# Connecteur.net
KiCad netlist of a schematic drawn in Altium Designer
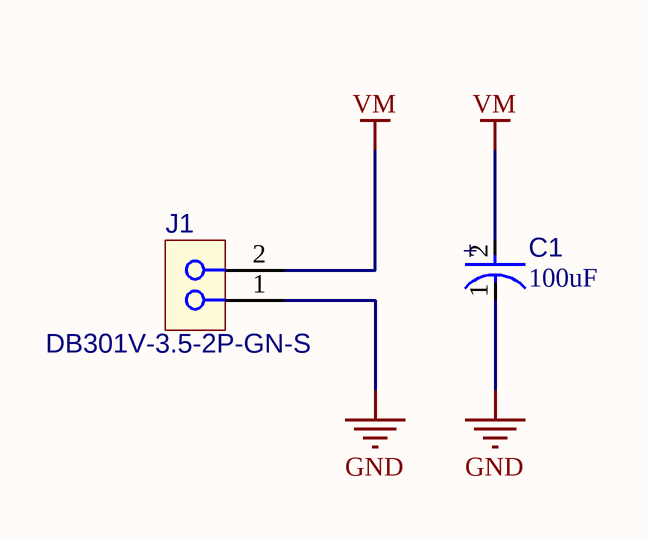
[diagram p0: Connecteur.SchDoc]

(export (version "E")
  (design (tool "Eeschema 10.0.6"))
  (components
    (comp (ref "C1")
      (value "100uF")
      (footprint "C_EL_D10MM-L11MM")
      (description "Capacitor type EL")
      (fields (field (name "TOLERANCE") "20%") (field (name "Comment") "CAP EL 100uF 63V 10MM"))
      (libsource (lib "TEP_243-Altium_DBLib") (part "capacitor_EL"))
    )
    (comp (ref "J1")
      (value "DB301V-3.5-2P-GN-S")
      (footprint "CONN_TERM_BLOCK_2POS_3mm5")
      (description "CONN TERM BLOCK 2POS 3.5mm pitch")
      (libsource (lib "TEP_243-AltiumLIB-Conn-TP-MH") (part "CONN-3MM5-2POS-TERM-BLOCK"))
    )
  )
  (nets
    (net (code "1") (name "GND") (class "Default")
      (node (ref "C1") (pin "1") (pinfunction "C_1") (pintype "passive"))
      (node (ref "J1") (pin "1") (pinfunction "1_1") (pintype "passive"))
    )
    (net (code "2") (name "VM") (class "Default")
      (node (ref "C1") (pin "2") (pinfunction "A_2") (pintype "passive"))
      (node (ref "J1") (pin "2") (pinfunction "2_2") (pintype "passive"))
    )
  )
)
